# tick-mini-mk-3_1.net
KiCad netlist of a schematic drawn in EAGLE
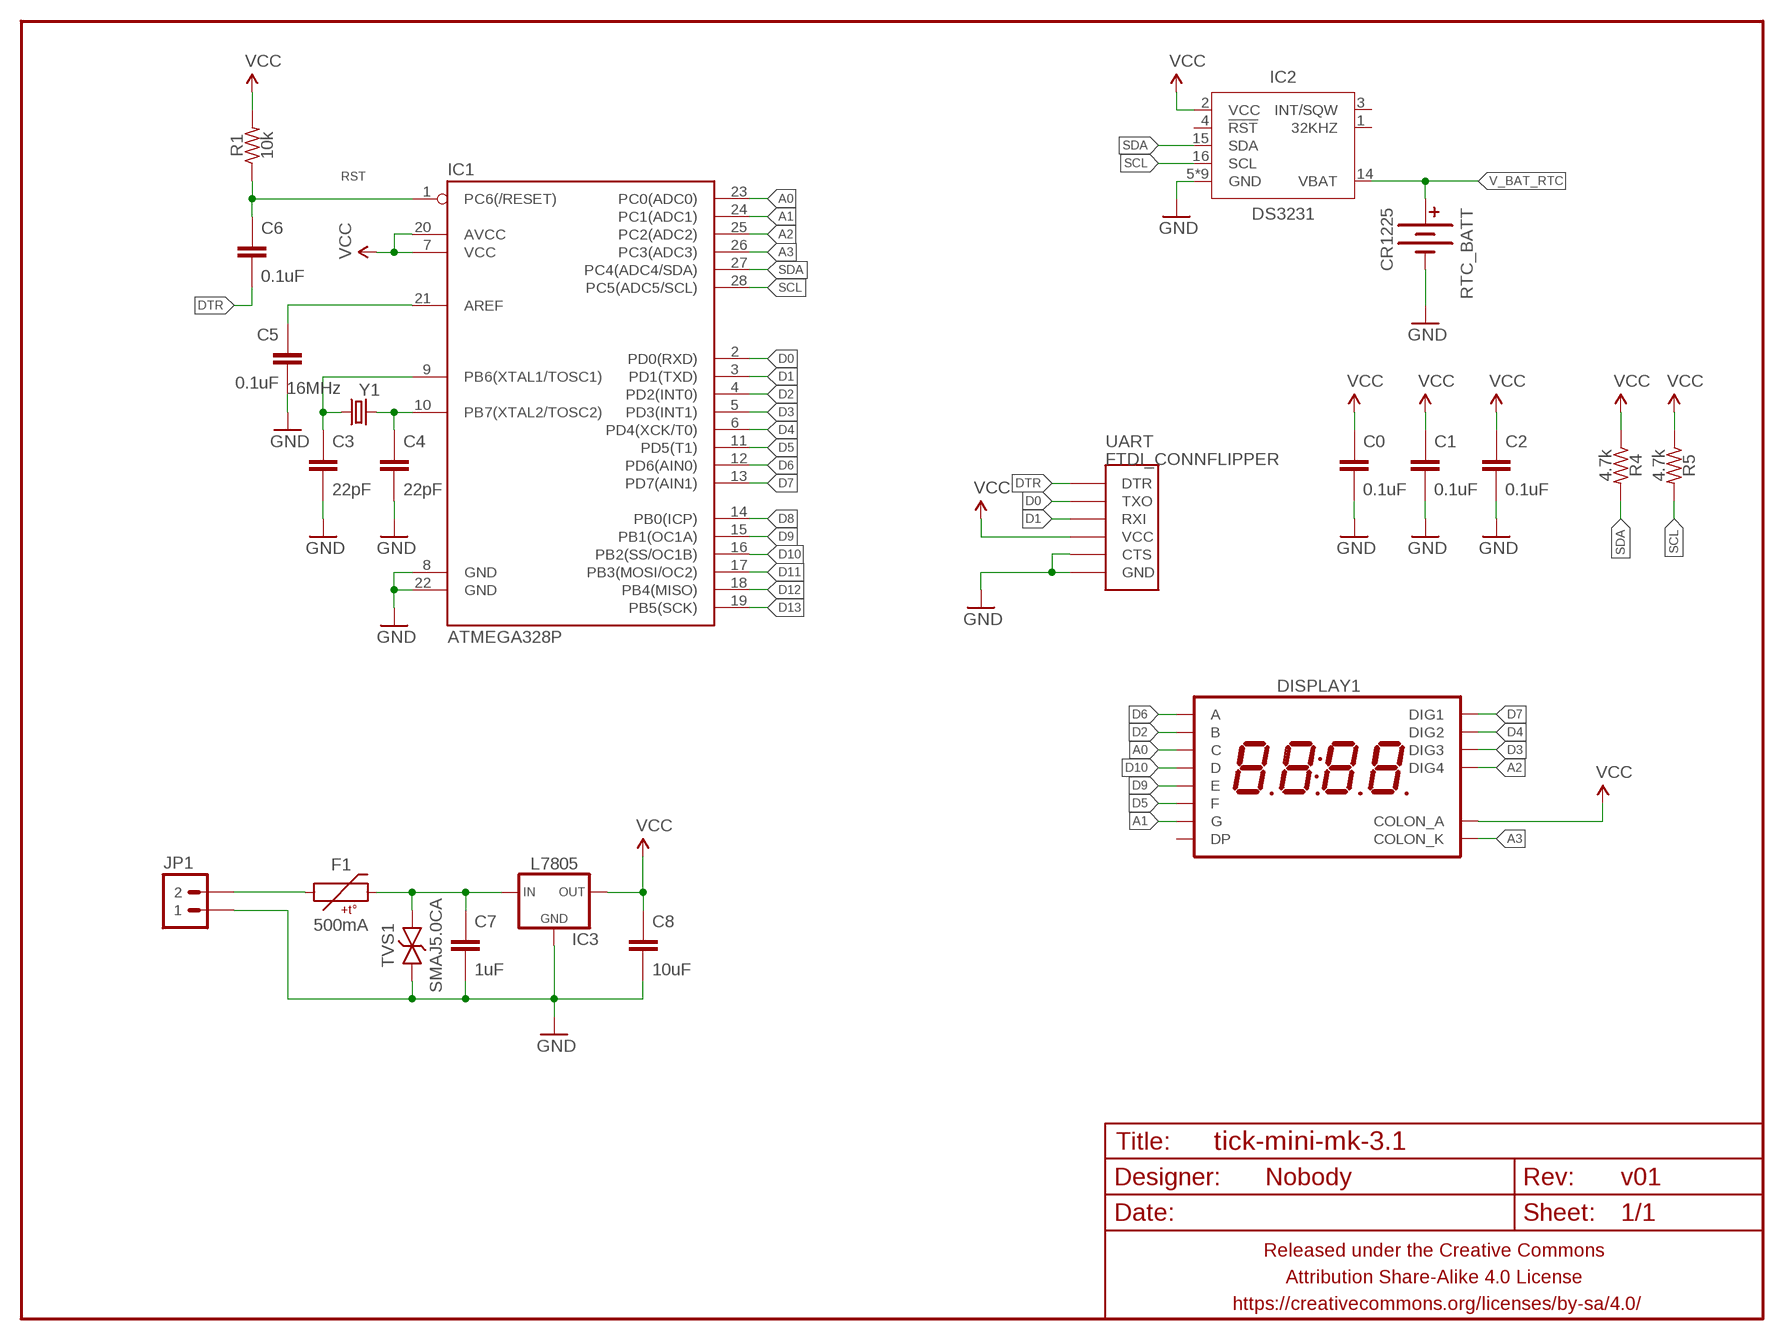
[diagram p0: schematic, sheet 1]

(export (version "E")
  (design (tool "Eeschema 10.0.6"))
  (components
    (comp (ref "C0")
      (value "0.1uF")
      (footprint "eagle-import:C0603")
      (libsource (lib "eagle-import") (part "CAPACITOR-CERAMICC0603"))
    )
    (comp (ref "C1")
      (value "0.1uF")
      (footprint "eagle-import:C0603")
      (libsource (lib "eagle-import") (part "CAPACITOR-CERAMICC0603"))
    )
    (comp (ref "C2")
      (value "0.1uF")
      (footprint "eagle-import:C0603")
      (libsource (lib "eagle-import") (part "CAPACITOR-CERAMICC0603"))
    )
    (comp (ref "C3")
      (value "22pF")
      (footprint "eagle-import:C0603")
      (libsource (lib "eagle-import") (part "CAPACITOR-CERAMICC0603"))
    )
    (comp (ref "C4")
      (value "22pF")
      (footprint "eagle-import:C0603")
      (libsource (lib "eagle-import") (part "CAPACITOR-CERAMICC0603"))
    )
    (comp (ref "C5")
      (value "0.1uF")
      (footprint "eagle-import:C0603")
      (libsource (lib "eagle-import") (part "CAPACITOR-CERAMICC0603"))
    )
    (comp (ref "C6")
      (value "0.1uF")
      (footprint "eagle-import:C0603")
      (libsource (lib "eagle-import") (part "CAPACITOR-CERAMICC0603"))
    )
    (comp (ref "C7")
      (value "1uF")
      (footprint "eagle-import:C1210")
      (libsource (lib "eagle-import") (part "CAPACITOR-CERAMICC1210"))
    )
    (comp (ref "C8")
      (value "10uF")
      (footprint "eagle-import:C1210")
      (libsource (lib "eagle-import") (part "CAPACITOR-CERAMICC1210"))
    )
    (comp (ref "DISPLAY1")
      (value "7SEG_4DIGIT_COLON14.2MM-CC-NS")
      (footprint "eagle-import:7SEG_4DIG_NS")
      (libsource (lib "eagle-import") (part "7SEG_4DIGIT_COLON14.2MM-CC-NS"))
    )
    (comp (ref "F1")
      (value "500mA")
      (footprint "eagle-import:PTC-1206")
      (libsource (lib "eagle-import") (part "PTCSMD"))
    )
    (comp (ref "FRAME1")
      (value "FRAME-LETTERNO_PACKAGE")
      (footprint "eagle-import:DUMMY")
      (fields (field (name "DESIGNER") "Nobody"))
      (libsource (lib "eagle-import") (part "FRAME-LETTERNO_PACKAGE"))
    )
    (comp (ref "IC1")
      (value "ATMEGA328P")
      (footprint "eagle-import:DIL28-3")
      (libsource (lib "eagle-import") (part "ATMEGA328P_PDIP"))
    )
    (comp (ref "IC2")
      (value "DS3231")
      (footprint "eagle-import:SO16W")
      (libsource (lib "eagle-import") (part "DS3231"))
    )
    (comp (ref "IC3")
      (value "L7805")
      (footprint "eagle-import:SO08")
      (libsource (lib "eagle-import") (part "V_REG_78XX"))
    )
    (comp (ref "JP1")
      (value "M02PTH-CENTERED-R+")
      (footprint "eagle-import:1X02-CENTER-R+")
      (libsource (lib "eagle-import") (part "M02PTH-CENTERED-R+"))
    )
    (comp (ref "R1")
      (value "10k")
      (footprint "eagle-import:R0603")
      (libsource (lib "eagle-import") (part "RESISTORR0603"))
    )
    (comp (ref "R4")
      (value "4.7k")
      (footprint "eagle-import:R0603")
      (libsource (lib "eagle-import") (part "RESISTORR0603"))
    )
    (comp (ref "R5")
      (value "4.7k")
      (footprint "eagle-import:R0603")
      (libsource (lib "eagle-import") (part "RESISTORR0603"))
    )
    (comp (ref "RTC_BATT")
      (value "CR1225")
      (footprint "eagle-import:BATTCON_12MM")
      (libsource (lib "eagle-import") (part "BATTERY12MM"))
    )
    (comp (ref "TVS1")
      (value "SMAJ5.0CA")
      (footprint "eagle-import:SMA-DIODE-TVS-BIDIR")
      (libsource (lib "eagle-import") (part "TVSSMA"))
    )
    (comp (ref "UART")
      (value "FTDI_CONNFLIPPER")
      (footprint "eagle-import:FTDI_CONN_FLIP")
      (libsource (lib "eagle-import") (part "FTDI_CONNFLIPPER"))
    )
    (comp (ref "Y1")
      (value "16MHz")
      (footprint "eagle-import:HC49U-V")
      (libsource (lib "eagle-import") (part "CRYSTALHC49UV"))
    )
  )
  (nets
    (net (code "1") (name "/RST") (class "Default")
      (node (ref "C6") (pin "1") (pinfunction "1_1") (pintype "passive"))
      (node (ref "IC1") (pin "1") (pinfunction "PC6(/RESET)_1") (pintype "bidirectional"))
      (node (ref "R1") (pin "1") (pinfunction "1_1") (pintype "passive"))
    )
    (net (code "2") (name "A0") (class "Default")
      (node (ref "DISPLAY1") (pin "P$4") (pinfunction "C_P$4") (pintype "passive"))
      (node (ref "IC1") (pin "23") (pinfunction "PC0(ADC0)_23") (pintype "bidirectional"))
    )
    (net (code "3") (name "A1") (class "Default")
      (node (ref "DISPLAY1") (pin "P$5") (pinfunction "G_P$5") (pintype "passive"))
      (node (ref "IC1") (pin "24") (pinfunction "PC1(ADC1)_24") (pintype "bidirectional"))
    )
    (net (code "4") (name "A2") (class "Default")
      (node (ref "DISPLAY1") (pin "P$6") (pinfunction "DIG4_P$6") (pintype "passive"))
      (node (ref "IC1") (pin "25") (pinfunction "PC2(ADC2)_25") (pintype "bidirectional"))
    )
    (net (code "5") (name "A3") (class "Default")
      (node (ref "DISPLAY1") (pin "P$7") (pinfunction "COLON_K_P$7") (pintype "passive"))
      (node (ref "IC1") (pin "26") (pinfunction "PC3(ADC3)_26") (pintype "bidirectional"))
    )
    (net (code "6") (name "D0") (class "Default")
      (node (ref "IC1") (pin "2") (pinfunction "PD0(RXD)_2") (pintype "bidirectional"))
      (node (ref "UART") (pin "TXO") (pinfunction "TXO_TXO") (pintype "bidirectional"))
    )
    (net (code "7") (name "D1") (class "Default")
      (node (ref "IC1") (pin "3") (pinfunction "PD1(TXD)_3") (pintype "bidirectional"))
      (node (ref "UART") (pin "RXI") (pinfunction "RXI_RXI") (pintype "bidirectional"))
    )
    (net (code "8") (name "D2") (class "Default")
      (node (ref "DISPLAY1") (pin "P$9") (pinfunction "B_P$9") (pintype "passive"))
      (node (ref "IC1") (pin "4") (pinfunction "PD2(INT0)_4") (pintype "bidirectional"))
    )
    (net (code "9") (name "D3") (class "Default")
      (node (ref "DISPLAY1") (pin "P$10") (pinfunction "DIG3_P$10") (pintype "passive"))
      (node (ref "IC1") (pin "5") (pinfunction "PD3(INT1)_5") (pintype "bidirectional"))
    )
    (net (code "10") (name "D4") (class "Default")
      (node (ref "DISPLAY1") (pin "P$11") (pinfunction "DIG2_P$11") (pintype "passive"))
      (node (ref "IC1") (pin "6") (pinfunction "PD4(XCK/T0)_6") (pintype "bidirectional"))
    )
    (net (code "11") (name "D5") (class "Default")
      (node (ref "DISPLAY1") (pin "P$12") (pinfunction "F_P$12") (pintype "passive"))
      (node (ref "IC1") (pin "11") (pinfunction "PD5(T1)_11") (pintype "bidirectional"))
    )
    (net (code "12") (name "D6") (class "Default")
      (node (ref "DISPLAY1") (pin "P$13") (pinfunction "A_P$13") (pintype "passive"))
      (node (ref "IC1") (pin "12") (pinfunction "PD6(AIN0)_12") (pintype "bidirectional"))
    )
    (net (code "13") (name "D7") (class "Default")
      (node (ref "DISPLAY1") (pin "P$14") (pinfunction "DIG1_P$14") (pintype "passive"))
      (node (ref "IC1") (pin "13") (pinfunction "PD7(AIN1)_13") (pintype "bidirectional"))
    )
    (net (code "14") (name "D8") (class "Default")
      (node (ref "IC1") (pin "14") (pinfunction "PB0(ICP)_14") (pintype "bidirectional"))
    )
    (net (code "15") (name "D9") (class "Default")
      (node (ref "DISPLAY1") (pin "P$1") (pinfunction "E_P$1") (pintype "passive"))
      (node (ref "IC1") (pin "15") (pinfunction "PB1(OC1A)_15") (pintype "bidirectional"))
    )
    (net (code "16") (name "D10") (class "Default")
      (node (ref "DISPLAY1") (pin "P$2") (pinfunction "D_P$2") (pintype "passive"))
      (node (ref "IC1") (pin "16") (pinfunction "PB2(SS/OC1B)_16") (pintype "bidirectional"))
    )
    (net (code "17") (name "D11") (class "Default")
      (node (ref "IC1") (pin "17") (pinfunction "PB3(MOSI/OC2)_17") (pintype "bidirectional"))
    )
    (net (code "18") (name "D12") (class "Default")
      (node (ref "IC1") (pin "18") (pinfunction "PB4(MISO)_18") (pintype "bidirectional"))
    )
    (net (code "19") (name "D13") (class "Default")
      (node (ref "IC1") (pin "19") (pinfunction "PB5(SCK)_19") (pintype "bidirectional"))
    )
    (net (code "20") (name "DTR") (class "Default")
      (node (ref "C6") (pin "2") (pinfunction "2_2") (pintype "passive"))
      (node (ref "UART") (pin "DTR") (pinfunction "DTR_DTR") (pintype "bidirectional"))
    )
    (net (code "21") (name "GND") (class "Default")
      (node (ref "C0") (pin "2") (pinfunction "2_2") (pintype "passive"))
      (node (ref "C1") (pin "2") (pinfunction "2_2") (pintype "passive"))
      (node (ref "C2") (pin "2") (pinfunction "2_2") (pintype "passive"))
      (node (ref "C3") (pin "2") (pinfunction "2_2") (pintype "passive"))
      (node (ref "C4") (pin "2") (pinfunction "2_2") (pintype "passive"))
      (node (ref "C5") (pin "2") (pinfunction "2_2") (pintype "passive"))
      (node (ref "C7") (pin "2") (pinfunction "2_2") (pintype "passive"))
      (node (ref "C8") (pin "2") (pinfunction "2_2") (pintype "passive"))
      (node (ref "IC1") (pin "22") (pinfunction "GND_22") (pintype "bidirectional"))
      (node (ref "IC1") (pin "8") (pinfunction "GND_8") (pintype "bidirectional"))
      (node (ref "IC2") (pin "10") (pinfunction "GND_10") (pintype "bidirectional"))
      (node (ref "IC2") (pin "11") (pinfunction "GND_11") (pintype "bidirectional"))
      (node (ref "IC2") (pin "12") (pinfunction "GND_12") (pintype "bidirectional"))
      (node (ref "IC2") (pin "13") (pinfunction "GND_13") (pintype "bidirectional"))
      (node (ref "IC2") (pin "5") (pinfunction "GND_5") (pintype "bidirectional"))
      (node (ref "IC2") (pin "6") (pinfunction "GND_6") (pintype "bidirectional"))
      (node (ref "IC2") (pin "7") (pinfunction "GND_7") (pintype "bidirectional"))
      (node (ref "IC2") (pin "8") (pinfunction "GND_8") (pintype "bidirectional"))
      (node (ref "IC2") (pin "9") (pinfunction "GND_9") (pintype "bidirectional"))
      (node (ref "IC3") (pin "2") (pinfunction "GND_2") (pintype "bidirectional"))
      (node (ref "IC3") (pin "3") (pinfunction "GND_3") (pintype "bidirectional"))
      (node (ref "IC3") (pin "4") (pinfunction "GND_4") (pintype "bidirectional"))
      (node (ref "IC3") (pin "5") (pinfunction "GND_5") (pintype "bidirectional"))
      (node (ref "IC3") (pin "6") (pinfunction "GND_6") (pintype "bidirectional"))
      (node (ref "IC3") (pin "7") (pinfunction "GND_7") (pintype "bidirectional"))
      (node (ref "JP1") (pin "1") (pinfunction "1_1") (pintype "passive"))
      (node (ref "RTC_BATT") (pin "GND") (pinfunction "-_GND") (pintype "power_in"))
      (node (ref "TVS1") (pin "1") (pinfunction "1_1") (pintype "passive"))
      (node (ref "UART") (pin "CTS") (pinfunction "CTS_CTS") (pintype "bidirectional"))
      (node (ref "UART") (pin "GND") (pinfunction "GND_GND") (pintype "bidirectional"))
    )
    (net (code "22") (name "Net-(F1-Pad1)") (class "Default")
      (node (ref "F1") (pin "1") (pinfunction "1_1") (pintype "passive"))
      (node (ref "JP1") (pin "2") (pinfunction "2_2") (pintype "passive"))
    )
    (net (code "23") (name "Net-(IC1-AREF)") (class "Default")
      (node (ref "C5") (pin "1") (pinfunction "1_1") (pintype "passive"))
      (node (ref "IC1") (pin "21") (pinfunction "AREF_21") (pintype "bidirectional"))
    )
    (net (code "24") (name "Net-(IC1-PB6(XTAL1{slash}TOSC1))") (class "Default")
      (node (ref "C3") (pin "1") (pinfunction "1_1") (pintype "passive"))
      (node (ref "IC1") (pin "9") (pinfunction "PB6(XTAL1/TOSC1)_9") (pintype "bidirectional"))
      (node (ref "Y1") (pin "2") (pinfunction "2_2") (pintype "passive"))
    )
    (net (code "25") (name "Net-(IC1-PB7(XTAL2{slash}TOSC2))") (class "Default")
      (node (ref "C4") (pin "1") (pinfunction "1_1") (pintype "passive"))
      (node (ref "IC1") (pin "10") (pinfunction "PB7(XTAL2/TOSC2)_10") (pintype "bidirectional"))
      (node (ref "Y1") (pin "1") (pinfunction "1_1") (pintype "passive"))
    )
    (net (code "26") (name "Net-(IC3-IN)") (class "Default")
      (node (ref "C7") (pin "1") (pinfunction "1_1") (pintype "passive"))
      (node (ref "F1") (pin "2") (pinfunction "2_2") (pintype "passive"))
      (node (ref "IC3") (pin "8") (pinfunction "IN_8") (pintype "bidirectional"))
      (node (ref "TVS1") (pin "2") (pinfunction "2_2") (pintype "passive"))
    )
    (net (code "27") (name "SCL") (class "Default")
      (node (ref "IC1") (pin "28") (pinfunction "PC5(ADC5/SCL)_28") (pintype "bidirectional"))
      (node (ref "IC2") (pin "16") (pinfunction "SCL_16") (pintype "bidirectional"))
      (node (ref "R5") (pin "2") (pinfunction "2_2") (pintype "passive"))
    )
    (net (code "28") (name "SDA") (class "Default")
      (node (ref "IC1") (pin "27") (pinfunction "PC4(ADC4/SDA)_27") (pintype "bidirectional"))
      (node (ref "IC2") (pin "15") (pinfunction "SDA_15") (pintype "bidirectional"))
      (node (ref "R4") (pin "2") (pinfunction "2_2") (pintype "passive"))
    )
    (net (code "29") (name "VCC") (class "Default")
      (node (ref "C0") (pin "1") (pinfunction "1_1") (pintype "passive"))
      (node (ref "C1") (pin "1") (pinfunction "1_1") (pintype "passive"))
      (node (ref "C2") (pin "1") (pinfunction "1_1") (pintype "passive"))
      (node (ref "C8") (pin "1") (pinfunction "1_1") (pintype "passive"))
      (node (ref "DISPLAY1") (pin "P$8") (pinfunction "COLON_A_P$8") (pintype "passive"))
      (node (ref "IC1") (pin "20") (pinfunction "AVCC_20") (pintype "bidirectional"))
      (node (ref "IC1") (pin "7") (pinfunction "VCC_7") (pintype "bidirectional"))
      (node (ref "IC2") (pin "2") (pinfunction "VCC_2") (pintype "bidirectional"))
      (node (ref "IC3") (pin "1") (pinfunction "OUT_1") (pintype "bidirectional"))
      (node (ref "R1") (pin "2") (pinfunction "2_2") (pintype "passive"))
      (node (ref "R4") (pin "1") (pinfunction "1_1") (pintype "passive"))
      (node (ref "R5") (pin "1") (pinfunction "1_1") (pintype "passive"))
      (node (ref "UART") (pin "VCC") (pinfunction "VCC_VCC") (pintype "bidirectional"))
    )
    (net (code "30") (name "V_BAT_RTC") (class "Default")
      (node (ref "IC2") (pin "14") (pinfunction "VBAT_14") (pintype "bidirectional"))
      (node (ref "RTC_BATT") (pin "PWR@1") (pinfunction "+_PWR@1") (pintype "power_in"))
    )
    (net (code "31") (name "unconnected-(DISPLAY1-DP-PadP$3)") (class "Default")
      (node (ref "DISPLAY1") (pin "P$3") (pinfunction "DP_P$3") (pintype "passive"))
    )
    (net (code "32") (name "unconnected-(IC2-32KHZ-Pad1)") (class "Default")
      (node (ref "IC2") (pin "1") (pinfunction "32KHZ_1") (pintype "bidirectional"))
    )
    (net (code "33") (name "unconnected-(IC2-INT{slash}SQW-Pad3)") (class "Default")
      (node (ref "IC2") (pin "3") (pinfunction "INT/SQW_3") (pintype "bidirectional"))
    )
    (net (code "34") (name "unconnected-(IC2-~{RST}-Pad4)") (class "Default")
      (node (ref "IC2") (pin "4") (pinfunction "~{RST}_4") (pintype "bidirectional"))
    )
  )
)
